# STC16.net
KiCad netlist of a schematic drawn in Altium Designer
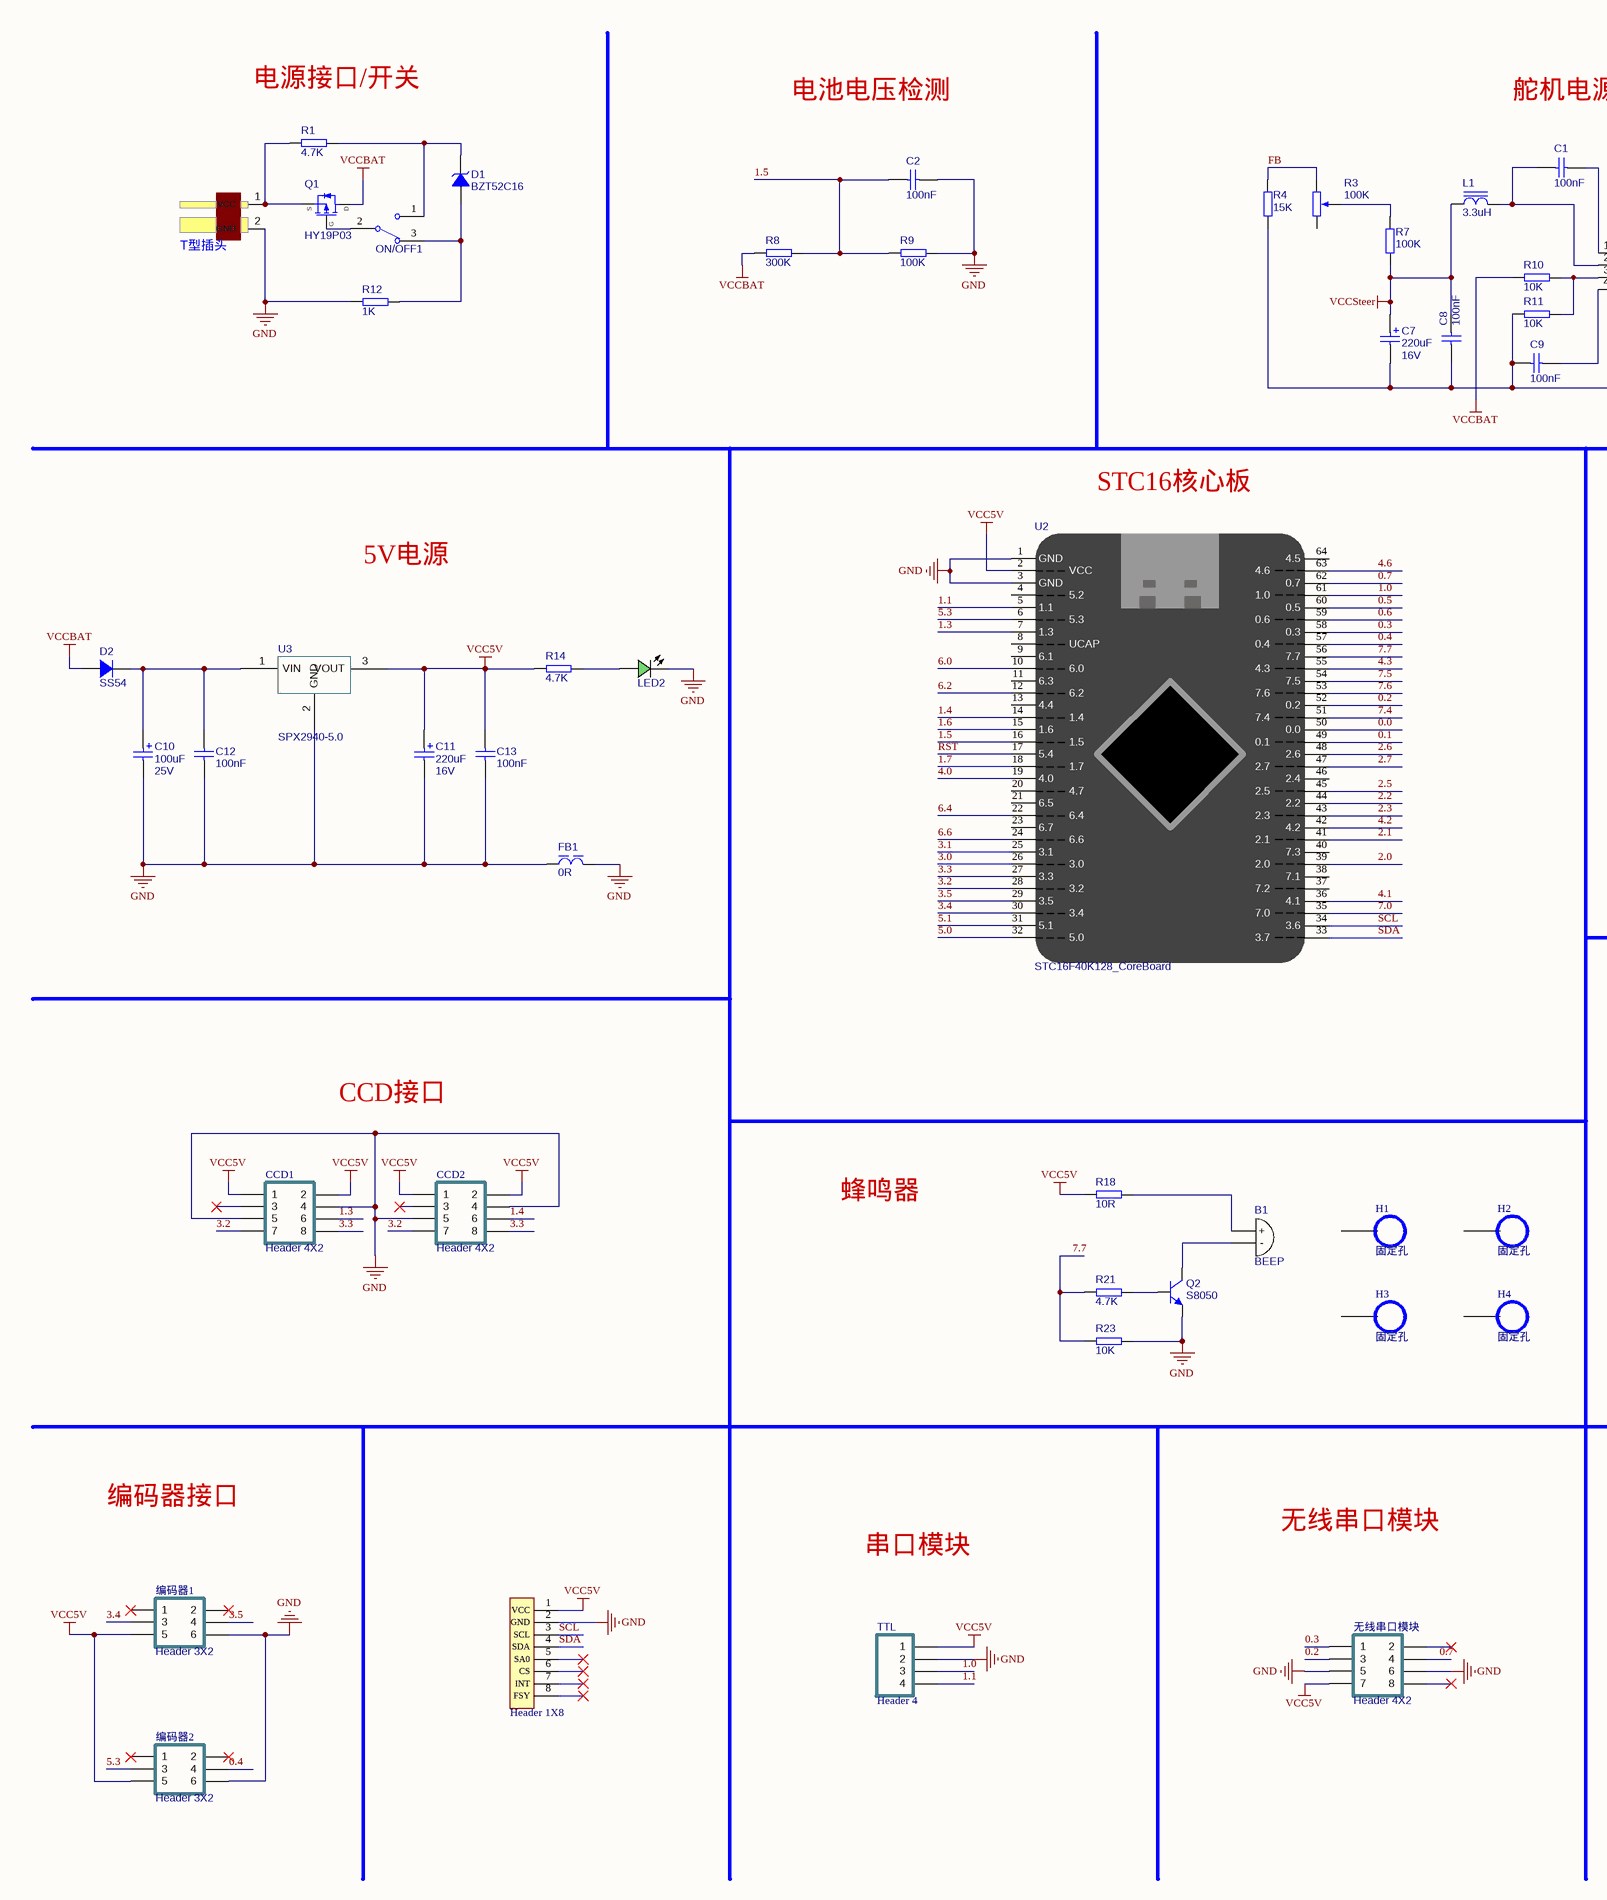
[diagram p0: STC16.SchDoc, left]
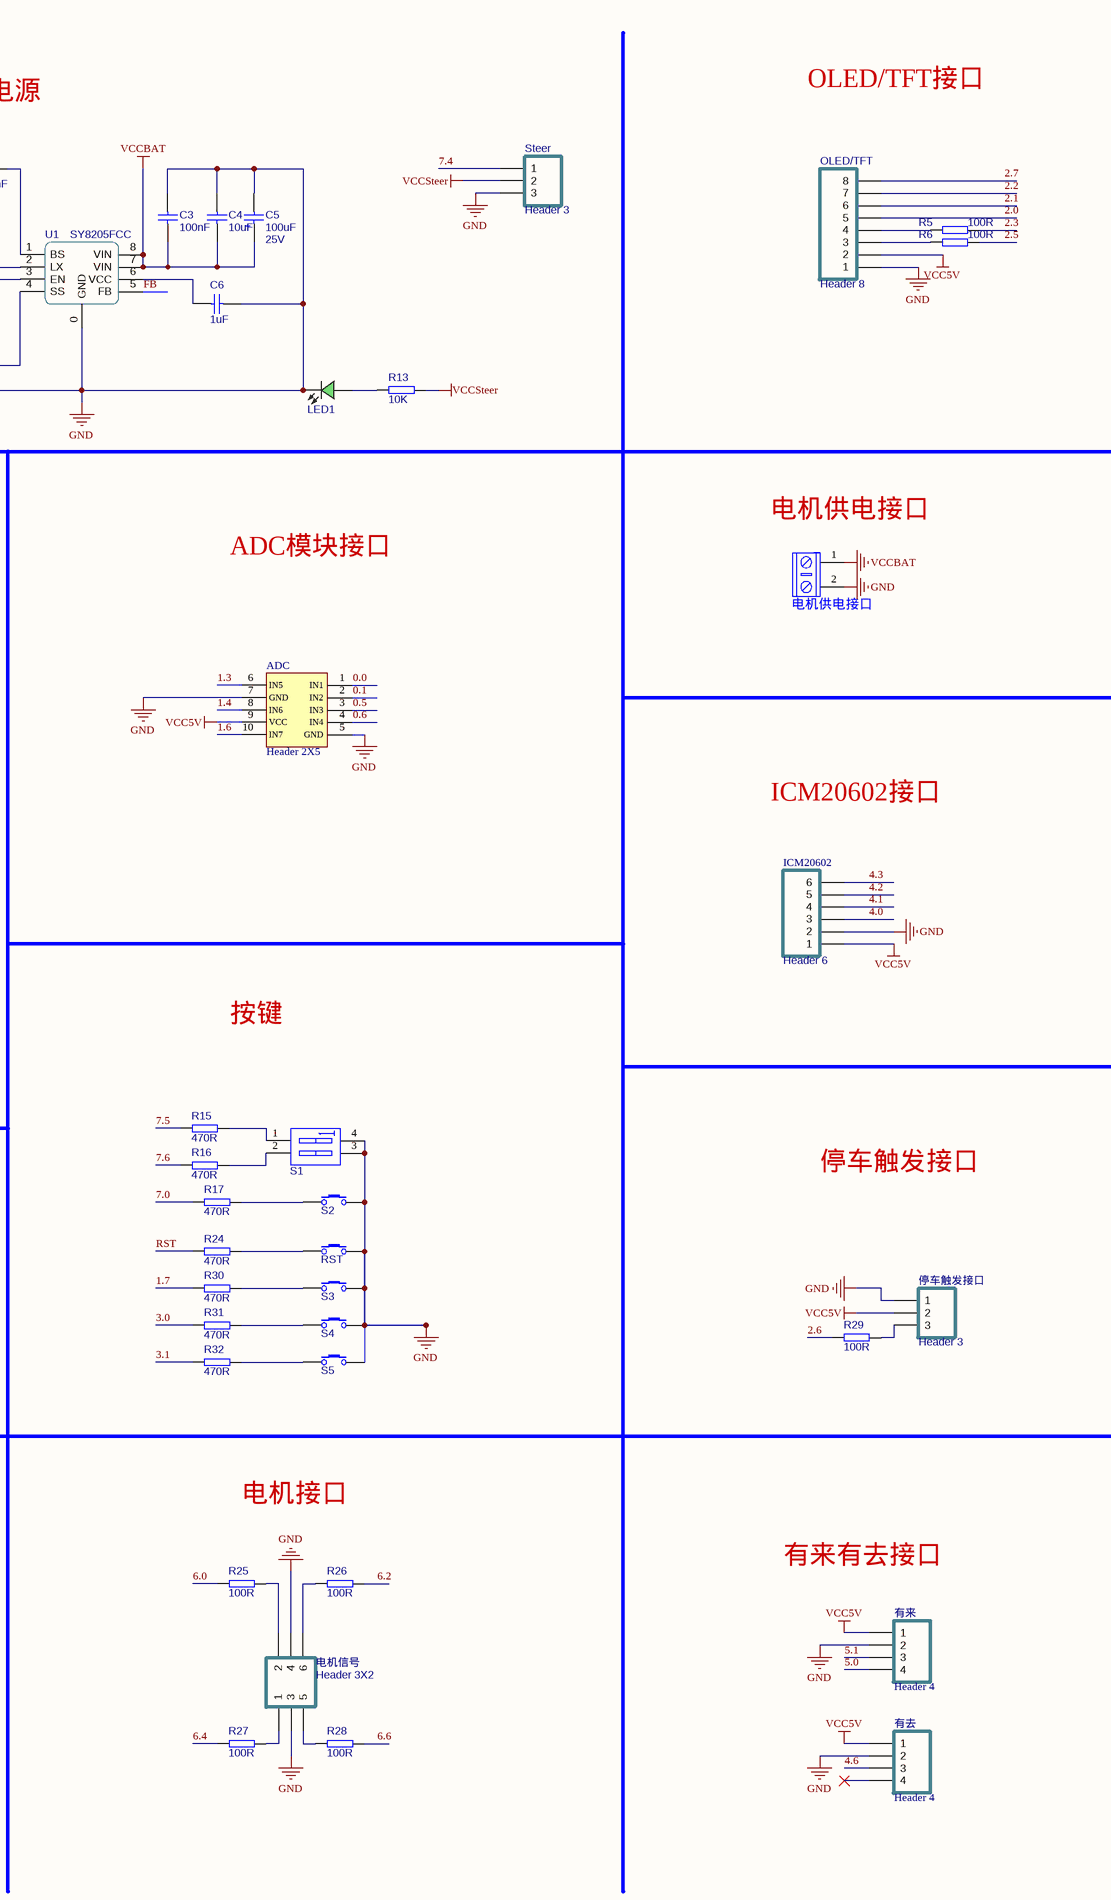
[diagram p1: STC16.SchDoc, right]

(export (version "E")
  (design (tool "Eeschema 10.0.6"))
  (components
    (comp (ref "ADC") (value "Header 2X5") (footprint "HDR2X5") (libsource (lib "STC16") (part "Header 2X5")))
    (comp (ref "B1")
      (value "BEEP")
      (footprint "BEEP 9x5.5mm")
      (description "蜂鸣器")
      (libsource (lib "STC16") (part "BEEP"))
    )
    (comp (ref "C1")
      (value "100nF")
      (footprint "0603_C")
      (description "贴片电容100nF")
      (fields
        (field (name "VOLTAGE") "50V")
        (field (name "TOLERANCE") "±10%")
        (field (name "PUBLISHER") "Altium Limited")
      )
      (libsource (lib "STC16") (part "Cap-Chip"))
    )
    (comp (ref "C2")
      (value "100nF")
      (footprint "0603_C")
      (description "贴片电容100nF")
      (fields
        (field (name "VOLTAGE") "50V")
        (field (name "TOLERANCE") "±10%")
        (field (name "PUBLISHER") "Altium Limited")
      )
      (libsource (lib "STC16") (part "Cap-Chip"))
    )
    (comp (ref "C3")
      (value "100nF")
      (footprint "0603_C")
      (description "贴片电容100nF")
      (fields
        (field (name "VOLTAGE") "50V")
        (field (name "TOLERANCE") "±10%")
        (field (name "PUBLISHER") "Altium Limited")
      )
      (libsource (lib "STC16") (part "Cap-Chip"))
    )
    (comp (ref "C4")
      (value "10uF")
      (footprint "0603_C")
      (description "贴片电容10uF")
      (fields
        (field (name "VOLTAGE") "50V")
        (field (name "TOLERANCE") "±10%")
        (field (name "PUBLISHER") "Altium Limited")
      )
      (libsource (lib "STC16") (part "Cap-Chip_2"))
    )
    (comp (ref "C5")
      (value "100uF")
      (footprint "CAPS6.3")
      (description "Polarized Capacitor (Radial) 100uF，25V")
      (fields
        (field (name "VOLTAGE") "25V")
        (field (name "Comment") "100uF 25V")
        (field (name "PUBLISHER") "Altium Limited")
      )
      (libsource (lib "STC16") (part "Cap-Solid"))
    )
    (comp (ref "C6")
      (value "1uF")
      (footprint "0603_C")
      (description "贴片电容1uF")
      (fields
        (field (name "VOLTAGE") "50V")
        (field (name "TOLERANCE") "±10%")
        (field (name "PUBLISHER") "Altium Limited")
      )
      (libsource (lib "STC16") (part "Cap-Chip_1"))
    )
    (comp (ref "C7")
      (value "220uF")
      (footprint "CAPS6.3")
      (description "Polarized Capacitor (Radial)  220uF 16V")
      (fields
        (field (name "VOLTAGE") "16V")
        (field (name "Comment") "220uF 16V")
        (field (name "PUBLISHER") "Altium Limited")
      )
      (libsource (lib "STC16") (part "Cap-Solid_1"))
    )
    (comp (ref "C8")
      (value "100nF")
      (footprint "0603_C")
      (description "贴片电容100nF")
      (fields
        (field (name "VOLTAGE") "50V")
        (field (name "TOLERANCE") "±10%")
        (field (name "PUBLISHER") "Altium Limited")
      )
      (libsource (lib "STC16") (part "Cap-Chip"))
    )
    (comp (ref "C9")
      (value "100nF")
      (footprint "0603_C")
      (description "贴片电容10uF")
      (fields
        (field (name "VOLTAGE") "50V")
        (field (name "TOLERANCE") "±10%")
        (field (name "PUBLISHER") "Altium Limited")
      )
      (libsource (lib "STC16") (part "Cap-Chip_2"))
    )
    (comp (ref "C10")
      (value "100uF")
      (footprint "CAPS6.3")
      (description "Polarized Capacitor (Radial) 100uF，25V")
      (fields
        (field (name "VOLTAGE") "25V")
        (field (name "Comment") "100uF 25V")
        (field (name "PUBLISHER") "Altium Limited")
      )
      (libsource (lib "STC16") (part "Cap-Solid"))
    )
    (comp (ref "C11")
      (value "220uF")
      (footprint "CAPS6.3")
      (description "Polarized Capacitor (Radial)  220uF 16V")
      (fields
        (field (name "VOLTAGE") "16V")
        (field (name "Comment") "220uF 16V")
        (field (name "PUBLISHER") "Altium Limited")
      )
      (libsource (lib "STC16") (part "Cap-Solid_1"))
    )
    (comp (ref "C12")
      (value "100nF")
      (footprint "0603_C")
      (description "贴片电容100nF")
      (fields
        (field (name "VOLTAGE") "50V")
        (field (name "TOLERANCE") "±10%")
        (field (name "PUBLISHER") "Altium Limited")
      )
      (libsource (lib "STC16") (part "Cap-Chip"))
    )
    (comp (ref "C13")
      (value "100nF")
      (footprint "0603_C")
      (description "贴片电容100nF")
      (fields
        (field (name "VOLTAGE") "50V")
        (field (name "TOLERANCE") "±10%")
        (field (name "PUBLISHER") "Altium Limited")
      )
      (libsource (lib "STC16") (part "Cap-Chip"))
    )
    (comp (ref "CCD1")
      (value "Header 4X2")
      (footprint "Female-Header-2.54-SMD-8")
      (description "Header, 4-Pin, Dual row")
      (fields (field (name "PUBLISHER") "Altium Limited"))
      (libsource (lib "STC16") (part "Header 4X2"))
    )
    (comp (ref "CCD2")
      (value "Header 4X2")
      (footprint "Female-Header-2.54-SMD-8")
      (description "Header, 4-Pin, Dual row")
      (fields (field (name "PUBLISHER") "Altium Limited"))
      (libsource (lib "STC16") (part "Header 4X2"))
    )
    (comp (ref "D1")
      (value "BZT52C16")
      (footprint "SOD-123-L")
      (description "TRANSIENT VOLTAGE  SUPPRESSOR DIODE")
      (fields (field (name "PUBLISHER") "Altium Limited"))
      (libsource (lib "STC16") (part "Diode TVS Uni-Dir"))
    )
    (comp (ref "D2")
      (value "SS54")
      (footprint "SMA[DO-214AC]")
      (description "普通二极管 Diode")
      (fields (field (name "PUBLISHER") "Altium Limited"))
      (libsource (lib "STC16") (part "Diode"))
    )
    (comp (ref "DCIN1")
      (value "T型插头")
      (footprint "Wired T-Header ThroughHole")
      (libsource (lib "STC16") (part "T_Header"))
    )
    (comp (ref "DCOUT1")
      (value "电机供电接口")
      (footprint "KF/WJ/DG 301-2p-5.0mm")
      (description "接线端子 2Pin")
      (libsource (lib "STC16") (part "KF/WJ/DG 30x"))
    )
    (comp (ref "FB1")
      (value "0R")
      (footprint "0603_R")
      (description "Chip Inductor, Ferrite-Core, Silkscreen Border")
      (fields (field (name "PUBLISHER") "Altium Limited"))
      (libsource (lib "STC16") (part "Ind Chip 2"))
    )
    (comp (ref "H1") (value "固定孔") (footprint "铜柱孔3") (libsource (lib "智能电子导盲系统") (part "固定孔")))
    (comp (ref "H2") (value "固定孔") (footprint "铜柱孔3") (libsource (lib "智能电子导盲系统") (part "固定孔")))
    (comp (ref "H3") (value "固定孔") (footprint "铜柱孔3") (libsource (lib "智能电子导盲系统") (part "固定孔")))
    (comp (ref "H4") (value "固定孔") (footprint "铜柱孔3") (libsource (lib "智能电子导盲系统") (part "固定孔")))
    (comp (ref "ICM20602")
      (value "Header 6")
      (footprint "HDR1X6")
      (description "Header, 6-Pin")
      (fields (field (name "PUBLISHER") "Altium Limited"))
      (libsource (lib "STC16") (part "Header 6"))
    )
    (comp (ref "L1")
      (value "3.3uH")
      (footprint "0630 TPC 7*7*3")
      (description "Power Inductor, Ferrite-Core")
      (fields (field (name "PUBLISHER") "Altium Limited"))
      (libsource (lib "STC16") (part "Ind Power"))
    )
    (comp (ref "LED1")
      (value "GREEN")
      (footprint "LEDC1608(0603)")
      (description "Typical Chip LED")
      (fields (field (name "PUBLISHER") "Altium Limited"))
      (libsource (lib "STC16") (part "LED Chip Green"))
    )
    (comp (ref "LED2")
      (value "GREEN")
      (footprint "LEDC1608(0603)")
      (description "Typical Chip LED")
      (fields (field (name "PUBLISHER") "Altium Limited"))
      (libsource (lib "STC16") (part "LED Chip Green"))
    )
    (comp (ref "MPU") (value "Header 1X8") (footprint "HDR1X8") (libsource (lib "STC16") (part "Header 1X8")))
    (comp (ref "OLED/TFT")
      (value "Header 8")
      (footprint "HDR1X8")
      (description "Header, 8-Pin")
      (fields (field (name "PUBLISHER") "Altium Limited"))
      (libsource (lib "STC16") (part "Header 8"))
    )
    (comp (ref "ON/OFF1")
      (value "SW-SPDT")
      (footprint "SS12D10")
      (description "单刀双掷开关 3脚船型、钮子、拨动开关 SPDT Subminiature Toggle Switch")
      (fields (field (name "PUBLISHER") "Altium Limited"))
      (libsource (lib "STC16") (part "SW-SPDT"))
    )
    (comp (ref "Q1")
      (value "HY19P03")
      (footprint "TO-252AA")
      (description "HY19P03 P-Channel MOSFET")
      (libsource (lib "STC16") (part "HY19P03"))
    )
    (comp (ref "Q2")
      (value "S8050")
      (footprint "SOT-23")
      (description "Discrete NPN Bipolar Transistor")
      (fields (field (name "PARTNUMBER") "S8050") (field (name "PUBLISHER") "Altium Limited"))
      (libsource (lib "STC16") (part "NPN S8050"))
    )
    (comp (ref "R1")
      (value "4.7K")
      (footprint "0603_R")
      (description "贴片电阻4.7K")
      (fields
        (field (name "TOLERANCE") "±1%")
        (field (name "Comment") "4.7K ±1%")
        (field (name "PUBLISHER") "Altium Limited")
      )
      (libsource (lib "STC16") (part "Res-Chip"))
    )
    (comp (ref "R3")
      (value "100K")
      (footprint "RESPOT3296")
      (description "可调电阻")
      (libsource (lib "STC16") (part "Res Adj 3p"))
    )
    (comp (ref "R4")
      (value "15K")
      (footprint "0603_R")
      (description "贴片电阻15K")
      (fields
        (field (name "TOLERANCE") "±1%")
        (field (name "Comment") "15K ±1%")
        (field (name "PUBLISHER") "Altium Limited")
      )
      (libsource (lib "SEEKFREE_Device") (part "Res-Chip_2"))
    )
    (comp (ref "R5")
      (value "100R")
      (footprint "0603_R")
      (description "贴片电阻100R")
      (fields
        (field (name "TOLERANCE") "±1%")
        (field (name "Comment") "100R ±1%")
        (field (name "PUBLISHER") "Altium Limited")
      )
      (libsource (lib "STC16") (part "Res-Chip_5"))
    )
    (comp (ref "R6")
      (value "100R")
      (footprint "0603_R")
      (description "贴片电阻100R")
      (fields
        (field (name "TOLERANCE") "±1%")
        (field (name "Comment") "100R ±1%")
        (field (name "PUBLISHER") "Altium Limited")
      )
      (libsource (lib "STC16") (part "Res-Chip_5"))
    )
    (comp (ref "R7")
      (value "100K")
      (footprint "0603_R")
      (description "贴片电阻10K")
      (fields
        (field (name "TOLERANCE") "±1%")
        (field (name "Comment") "100K ±1%")
        (field (name "PUBLISHER") "Altium Limited")
      )
      (libsource (lib "SEEKFREE_Device") (part "Res-Chip_3"))
    )
    (comp (ref "R8")
      (value "300K")
      (footprint "0603_R")
      (description "贴片电阻")
      (fields
        (field (name "TOLERANCE") "±1%")
        (field (name "Comment") "300K ±1%")
        (field (name "PUBLISHER") "Altium Limited")
      )
      (libsource (lib "STC16") (part "Res-Chip_7"))
    )
    (comp (ref "R9")
      (value "100K")
      (footprint "0603_R")
      (description "贴片电阻100K")
      (fields
        (field (name "TOLERANCE") "±1%")
        (field (name "Comment") "100K ±1%")
        (field (name "PUBLISHER") "Altium Limited")
      )
      (libsource (lib "STC16") (part "Res-Chip_1"))
    )
    (comp (ref "R10")
      (value "10K")
      (footprint "0603_R")
      (description "贴片电阻10K")
      (fields
        (field (name "TOLERANCE") "±1%")
        (field (name "Comment") "10K ±1%")
        (field (name "PUBLISHER") "Altium Limited")
      )
      (libsource (lib "SEEKFREE_Device") (part "Res-Chip_3"))
    )
    (comp (ref "R11")
      (value "10K")
      (footprint "0603_R")
      (description "贴片电阻10K")
      (fields
        (field (name "TOLERANCE") "±1%")
        (field (name "Comment") "10K ±1%")
        (field (name "PUBLISHER") "Altium Limited")
      )
      (libsource (lib "SEEKFREE_Device") (part "Res-Chip_3"))
    )
    (comp (ref "R12")
      (value "1K")
      (footprint "0603_R")
      (description "贴片电阻1K")
      (fields
        (field (name "TOLERANCE") "±1%")
        (field (name "Comment") "1K ±1%")
        (field (name "PUBLISHER") "Altium Limited")
      )
      (libsource (lib "STC16") (part "Res-Chip_4"))
    )
    (comp (ref "R13")
      (value "10K")
      (footprint "0603_R")
      (description "贴片电阻10K")
      (fields
        (field (name "TOLERANCE") "±1%")
        (field (name "Comment") "10K ±1%")
        (field (name "PUBLISHER") "Altium Limited")
      )
      (libsource (lib "SEEKFREE_Device") (part "Res-Chip_3"))
    )
    (comp (ref "R14")
      (value "4.7K")
      (footprint "0603_R")
      (description "贴片电阻4.7K")
      (fields
        (field (name "TOLERANCE") "±1%")
        (field (name "Comment") "4.7K ±1%")
        (field (name "PUBLISHER") "Altium Limited")
      )
      (libsource (lib "STC16") (part "Res-Chip"))
    )
    (comp (ref "R15")
      (value "470R")
      (footprint "0603_R")
      (description "贴片电阻")
      (fields
        (field (name "TOLERANCE") "±1%")
        (field (name "Comment") "470R ±1%")
        (field (name "PUBLISHER") "Altium Limited")
      )
      (libsource (lib "STC16") (part "Res-Chip_8"))
    )
    (comp (ref "R16")
      (value "470R")
      (footprint "0603_R")
      (description "贴片电阻")
      (fields
        (field (name "TOLERANCE") "±1%")
        (field (name "Comment") "470R ±1%")
        (field (name "PUBLISHER") "Altium Limited")
      )
      (libsource (lib "STC16") (part "Res-Chip_8"))
    )
    (comp (ref "R17")
      (value "470R")
      (footprint "0603_R")
      (description "贴片电阻")
      (fields
        (field (name "TOLERANCE") "±1%")
        (field (name "Comment") "470R ±1%")
        (field (name "PUBLISHER") "Altium Limited")
      )
      (libsource (lib "STC16") (part "Res-Chip_8"))
    )
    (comp (ref "R18")
      (value "10R")
      (footprint "0603_R")
      (description "贴片电阻")
      (fields
        (field (name "TOLERANCE") "±1%")
        (field (name "Comment") "10R ±1%")
        (field (name "PUBLISHER") "Altium Limited")
      )
      (libsource (lib "STC16") (part "Res-Chip_6"))
    )
    (comp (ref "R21")
      (value "4.7K")
      (footprint "0603_R")
      (description "贴片电阻4.7K")
      (fields
        (field (name "TOLERANCE") "±1%")
        (field (name "Comment") "4.7K ±1%")
        (field (name "PUBLISHER") "Altium Limited")
      )
      (libsource (lib "STC16") (part "Res-Chip"))
    )
    (comp (ref "R23")
      (value "10K")
      (footprint "0603_R")
      (description "贴片电阻10K")
      (fields
        (field (name "TOLERANCE") "±1%")
        (field (name "Comment") "10K ±1%")
        (field (name "PUBLISHER") "Altium Limited")
      )
      (libsource (lib "STC16") (part "Res-Chip_3"))
    )
    (comp (ref "R24")
      (value "470R")
      (footprint "0603_R")
      (description "贴片电阻")
      (fields
        (field (name "TOLERANCE") "±1%")
        (field (name "Comment") "470R ±1%")
        (field (name "PUBLISHER") "Altium Limited")
      )
      (libsource (lib "STC16") (part "Res-Chip_8"))
    )
    (comp (ref "R25")
      (value "100R")
      (footprint "0603_R")
      (description "贴片电阻100R")
      (fields
        (field (name "TOLERANCE") "±1%")
        (field (name "Comment") "100R ±1%")
        (field (name "PUBLISHER") "Altium Limited")
      )
      (libsource (lib "STC16") (part "Res-Chip_5"))
    )
    (comp (ref "R26")
      (value "100R")
      (footprint "0603_R")
      (description "贴片电阻100R")
      (fields
        (field (name "TOLERANCE") "±1%")
        (field (name "Comment") "100R ±1%")
        (field (name "PUBLISHER") "Altium Limited")
      )
      (libsource (lib "STC16") (part "Res-Chip_5"))
    )
    (comp (ref "R27")
      (value "100R")
      (footprint "0603_R")
      (description "贴片电阻100R")
      (fields
        (field (name "TOLERANCE") "±1%")
        (field (name "Comment") "100R ±1%")
        (field (name "PUBLISHER") "Altium Limited")
      )
      (libsource (lib "STC16") (part "Res-Chip_5"))
    )
    (comp (ref "R28")
      (value "100R")
      (footprint "0603_R")
      (description "贴片电阻100R")
      (fields
        (field (name "TOLERANCE") "±1%")
        (field (name "Comment") "100R ±1%")
        (field (name "PUBLISHER") "Altium Limited")
      )
      (libsource (lib "STC16") (part "Res-Chip_5"))
    )
    (comp (ref "R29")
      (value "100R")
      (footprint "0603_R")
      (description "贴片电阻100R")
      (fields
        (field (name "TOLERANCE") "±1%")
        (field (name "Comment") "100R ±1%")
        (field (name "PUBLISHER") "Altium Limited")
      )
      (libsource (lib "STC16") (part "Res-Chip_5"))
    )
    (comp (ref "R30")
      (value "470R")
      (footprint "0603_R")
      (description "贴片电阻")
      (fields
        (field (name "TOLERANCE") "±1%")
        (field (name "Comment") "470R ±1%")
        (field (name "PUBLISHER") "Altium Limited")
      )
      (libsource (lib "STC16") (part "Res-Chip_8"))
    )
    (comp (ref "R31")
      (value "470R")
      (footprint "0603_R")
      (description "贴片电阻")
      (fields
        (field (name "TOLERANCE") "±1%")
        (field (name "Comment") "470R ±1%")
        (field (name "PUBLISHER") "Altium Limited")
      )
      (libsource (lib "STC16") (part "Res-Chip_8"))
    )
    (comp (ref "R32")
      (value "470R")
      (footprint "0603_R")
      (description "贴片电阻")
      (fields
        (field (name "TOLERANCE") "±1%")
        (field (name "Comment") "470R ±1%")
        (field (name "PUBLISHER") "Altium Limited")
      )
      (libsource (lib "STC16") (part "Res-Chip_8"))
    )
    (comp (ref "RST")
      (value "Button")
      (footprint "PTS810-3*4-CurvePin")
      (description "按键")
      (fields (field (name "PUBLISHER") "Altium Limited"))
      (libsource (lib "STC16") (part "KEY"))
    )
    (comp (ref "S1")
      (value "SW DIP-2")
      (footprint "DIP4")
      (description "2位拨码开关")
      (fields (field (name "PUBLISHER") "Altium Limited"))
      (libsource (lib "STC16") (part "Code SW-2"))
    )
    (comp (ref "S2")
      (value "Button")
      (footprint "PTS810-3*4-CurvePin")
      (description "按键")
      (fields (field (name "PUBLISHER") "Altium Limited"))
      (libsource (lib "STC16") (part "KEY"))
    )
    (comp (ref "S3")
      (value "Button")
      (footprint "PTS810-3*4-CurvePin")
      (description "按键")
      (fields (field (name "PUBLISHER") "Altium Limited"))
      (libsource (lib "STC16") (part "KEY"))
    )
    (comp (ref "S4")
      (value "Button")
      (footprint "PTS810-3*4-CurvePin")
      (description "按键")
      (fields (field (name "PUBLISHER") "Altium Limited"))
      (libsource (lib "STC16") (part "KEY"))
    )
    (comp (ref "S5")
      (value "Button")
      (footprint "PTS810-3*4-CurvePin")
      (description "按键")
      (fields (field (name "PUBLISHER") "Altium Limited"))
      (libsource (lib "STC16") (part "KEY"))
    )
    (comp (ref "Steer")
      (value "Header 3")
      (footprint "HDR1X3")
      (description "Header, 3-Pin")
      (fields (field (name "PUBLISHER") "Altium Limited"))
      (libsource (lib "STC16") (part "Header 3"))
    )
    (comp (ref "TTL")
      (value "Header 4")
      (footprint "HDR1X4")
      (description "Header, 4-Pin")
      (fields (field (name "PUBLISHER") "Altium Limited"))
      (libsource (lib "") (part "Header 4_1"))
    )
    (comp (ref "U1")
      (value "SY8205FCC")
      (footprint "SOP-8E")
      (description "同步buck")
      (libsource (lib "STC16") (part "SY8205FCC"))
    )
    (comp (ref "U2")
      (value "STC16F40K128_CoreBoard")
      (footprint "STC16F40K128_CoreBoard")
      (description "逐飞科技 STC16F40K128核心板")
      (libsource (lib "STC16") (part "STC16F40K128_CoreBoard"))
    )
    (comp (ref "U3")
      (value "SPX2940-5.0")
      (footprint "TO-263-3")
      (description "5V LDO TO-263-3")
      (libsource (lib "STC16") (part "LM2940-5.0"))
    )
    (comp (ref "停车触发接口")
      (value "Header 3")
      (footprint "HDR1X3")
      (description "Header, 3-Pin")
      (fields (field (name "PUBLISHER") "Altium Limited"))
      (libsource (lib "STC16") (part "Header 3"))
    )
    (comp (ref "无线串口模块")
      (value "Header 4X2")
      (footprint "Female-Header-2.54-SMD-8")
      (description "Header, 4-Pin, Dual row")
      (fields (field (name "PUBLISHER") "Altium Limited"))
      (libsource (lib "STC16") (part "Header 4X2"))
    )
    (comp (ref "有去")
      (value "Header 4")
      (footprint "HDR1X4")
      (description "Header, 4-Pin")
      (fields (field (name "PUBLISHER") "Altium Limited"))
      (libsource (lib "STC16") (part "Header 4"))
    )
    (comp (ref "有来")
      (value "Header 4")
      (footprint "HDR1X4")
      (description "Header, 4-Pin")
      (fields (field (name "PUBLISHER") "Altium Limited"))
      (libsource (lib "STC16") (part "Header 4"))
    )
    (comp (ref "电机信号")
      (value "Header 3X2")
      (footprint "HDR2X3-M-SMT")
      (description "Header, 3-Pin, Dual row")
      (fields (field (name "PUBLISHER") "Altium Limited"))
      (libsource (lib "STC16") (part "Header 3X2"))
    )
    (comp (ref "编码器1")
      (value "Header 3X2")
      (footprint "HDR2X3-M-SMT")
      (description "Header, 3-Pin, Dual row")
      (fields (field (name "PUBLISHER") "Altium Limited"))
      (libsource (lib "") (part "Header 3X2_1"))
    )
    (comp (ref "编码器2")
      (value "Header 3X2")
      (footprint "HDR2X3-M-SMT")
      (description "Header, 3-Pin, Dual row")
      (fields (field (name "PUBLISHER") "Altium Limited"))
      (libsource (lib "") (part "Header 3X2_1"))
    )
  )
  (nets
    (net (code "1") (name "/0.0") (class "Default")
      (node (ref "ADC") (pin "1") (pinfunction "IN1_1") (pintype "passive"))
      (node (ref "U2") (pin "50") (pinfunction "0.0_50") (pintype "passive"))
    )
    (net (code "2") (name "/0.1") (class "Default")
      (node (ref "ADC") (pin "2") (pinfunction "IN2_2") (pintype "passive"))
      (node (ref "U2") (pin "49") (pinfunction "0.1_49") (pintype "passive"))
    )
    (net (code "3") (name "/0.2") (class "Default")
      (node (ref "U2") (pin "52") (pinfunction "0.2_52") (pintype "passive"))
      (node (ref "无线串口模块") (pin "3") (pinfunction "3_3") (pintype "passive"))
    )
    (net (code "4") (name "/0.3") (class "Default")
      (node (ref "U2") (pin "58") (pinfunction "0.3_58") (pintype "passive"))
      (node (ref "无线串口模块") (pin "1") (pinfunction "1_1") (pintype "passive"))
    )
    (net (code "5") (name "/0.4") (class "Default")
      (node (ref "U2") (pin "57") (pinfunction "0.4_57") (pintype "passive"))
      (node (ref "编码器2") (pin "4") (pinfunction "4_4") (pintype "passive"))
    )
    (net (code "6") (name "/0.5") (class "Default")
      (node (ref "ADC") (pin "3") (pinfunction "IN3_3") (pintype "passive"))
      (node (ref "U2") (pin "60") (pinfunction "0.5_60") (pintype "passive"))
    )
    (net (code "7") (name "/0.6") (class "Default")
      (node (ref "ADC") (pin "4") (pinfunction "IN4_4") (pintype "passive"))
      (node (ref "U2") (pin "59") (pinfunction "0.6_59") (pintype "passive"))
    )
    (net (code "8") (name "/0.7") (class "Default")
      (node (ref "U2") (pin "62") (pinfunction "0.7_62") (pintype "passive"))
      (node (ref "无线串口模块") (pin "4") (pinfunction "4_4") (pintype "passive"))
    )
    (net (code "9") (name "/1.0") (class "Default")
      (node (ref "TTL") (pin "3") (pinfunction "3_3") (pintype "passive"))
      (node (ref "U2") (pin "61") (pinfunction "1.0_61") (pintype "passive"))
    )
    (net (code "10") (name "/1.1") (class "Default")
      (node (ref "TTL") (pin "4") (pinfunction "4_4") (pintype "passive"))
      (node (ref "U2") (pin "5") (pinfunction "1.1_5") (pintype "passive"))
    )
    (net (code "11") (name "/1.3") (class "Default")
      (node (ref "ADC") (pin "6") (pinfunction "IN5_6") (pintype "passive"))
      (node (ref "CCD1") (pin "6") (pinfunction "6_6") (pintype "passive"))
      (node (ref "U2") (pin "7") (pinfunction "1.3_7") (pintype "passive"))
    )
    (net (code "12") (name "/1.4") (class "Default")
      (node (ref "ADC") (pin "8") (pinfunction "IN6_8") (pintype "passive"))
      (node (ref "CCD2") (pin "6") (pinfunction "6_6") (pintype "passive"))
      (node (ref "U2") (pin "14") (pinfunction "1.4_14") (pintype "passive"))
    )
    (net (code "13") (name "/1.5") (class "Default")
      (node (ref "C2") (pin "1") (pinfunction "1_1") (pintype "passive"))
      (node (ref "R8") (pin "2") (pinfunction "2_2") (pintype "passive"))
      (node (ref "R9") (pin "1") (pinfunction "1_1") (pintype "passive"))
      (node (ref "U2") (pin "16") (pinfunction "1.5_16") (pintype "passive"))
    )
    (net (code "14") (name "/1.6") (class "Default")
      (node (ref "ADC") (pin "10") (pinfunction "IN7_10") (pintype "passive"))
      (node (ref "U2") (pin "15") (pinfunction "1.6_15") (pintype "passive"))
    )
    (net (code "15") (name "/1.7") (class "Default")
      (node (ref "R30") (pin "1") (pinfunction "1_1") (pintype "passive"))
      (node (ref "U2") (pin "18") (pinfunction "1.7_18") (pintype "passive"))
    )
    (net (code "16") (name "/2.0") (class "Default")
      (node (ref "OLED/TFT") (pin "5") (pinfunction "5_5") (pintype "passive"))
      (node (ref "U2") (pin "39") (pinfunction "2.0_39") (pintype "passive"))
    )
    (net (code "17") (name "/2.1") (class "Default")
      (node (ref "OLED/TFT") (pin "6") (pinfunction "6_6") (pintype "passive"))
      (node (ref "U2") (pin "41") (pinfunction "2.1_41") (pintype "passive"))
    )
    (net (code "18") (name "/2.2") (class "Default")
      (node (ref "OLED/TFT") (pin "7") (pinfunction "7_7") (pintype "passive"))
      (node (ref "U2") (pin "44") (pinfunction "2.2_44") (pintype "passive"))
    )
    (net (code "19") (name "/2.3") (class "Default")
      (node (ref "R5") (pin "2") (pinfunction "2_2") (pintype "passive"))
      (node (ref "U2") (pin "43") (pinfunction "2.3_43") (pintype "passive"))
    )
    (net (code "20") (name "/2.5") (class "Default")
      (node (ref "R6") (pin "2") (pinfunction "2_2") (pintype "passive"))
      (node (ref "U2") (pin "45") (pinfunction "2.5_45") (pintype "passive"))
    )
    (net (code "21") (name "/2.6") (class "Default")
      (node (ref "R29") (pin "1") (pinfunction "1_1") (pintype "passive"))
      (node (ref "U2") (pin "48") (pinfunction "2.6_48") (pintype "passive"))
    )
    (net (code "22") (name "/2.7") (class "Default")
      (node (ref "OLED/TFT") (pin "8") (pinfunction "8_8") (pintype "passive"))
      (node (ref "U2") (pin "47") (pinfunction "2.7_47") (pintype "passive"))
    )
    (net (code "23") (name "/3.0") (class "Default")
      (node (ref "R31") (pin "1") (pinfunction "1_1") (pintype "passive"))
      (node (ref "U2") (pin "26") (pinfunction "3.0_26") (pintype "passive"))
    )
    (net (code "24") (name "/3.1") (class "Default")
      (node (ref "R32") (pin "1") (pinfunction "1_1") (pintype "passive"))
      (node (ref "U2") (pin "25") (pinfunction "3.1_25") (pintype "passive"))
    )
    (net (code "25") (name "/3.2") (class "Default")
      (node (ref "CCD1") (pin "7") (pinfunction "7_7") (pintype "passive"))
      (node (ref "CCD2") (pin "7") (pinfunction "7_7") (pintype "passive"))
      (node (ref "U2") (pin "28") (pinfunction "3.2_28") (pintype "passive"))
    )
    (net (code "26") (name "/3.3") (class "Default")
      (node (ref "CCD1") (pin "8") (pinfunction "8_8") (pintype "passive"))
      (node (ref "CCD2") (pin "8") (pinfunction "8_8") (pintype "passive"))
      (node (ref "U2") (pin "27") (pinfunction "3.3_27") (pintype "passive"))
    )
    (net (code "27") (name "/3.4") (class "Default")
      (node (ref "U2") (pin "30") (pinfunction "3.4_30") (pintype "passive"))
      (node (ref "编码器1") (pin "3") (pinfunction "3_3") (pintype "passive"))
    )
    (net (code "28") (name "/3.5") (class "Default")
      (node (ref "U2") (pin "29") (pinfunction "3.5_29") (pintype "passive"))
      (node (ref "编码器1") (pin "4") (pinfunction "4_4") (pintype "passive"))
    )
    (net (code "29") (name "/4.0") (class "Default")
      (node (ref "ICM20602") (pin "3") (pinfunction "3_3") (pintype "passive"))
      (node (ref "U2") (pin "19") (pinfunction "4.0_19") (pintype "passive"))
    )
    (net (code "30") (name "/4.1") (class "Default")
      (node (ref "ICM20602") (pin "4") (pinfunction "4_4") (pintype "passive"))
      (node (ref "U2") (pin "36") (pinfunction "4.1_36") (pintype "passive"))
    )
    (net (code "31") (name "/4.2") (class "Default")
      (node (ref "ICM20602") (pin "5") (pinfunction "5_5") (pintype "passive"))
      (node (ref "U2") (pin "42") (pinfunction "4.2_42") (pintype "passive"))
    )
    (net (code "32") (name "/4.3") (class "Default")
      (node (ref "ICM20602") (pin "6") (pinfunction "6_6") (pintype "passive"))
      (node (ref "U2") (pin "55") (pinfunction "4.3_55") (pintype "passive"))
    )
    (net (code "33") (name "/4.6") (class "Default")
      (node (ref "U2") (pin "63") (pinfunction "4.6_63") (pintype "passive"))
      (node (ref "有去") (pin "3") (pinfunction "3_3") (pintype "passive"))
    )
    (net (code "34") (name "/5.0") (class "Default")
      (node (ref "U2") (pin "32") (pinfunction "5.0_32") (pintype "passive"))
      (node (ref "有来") (pin "4") (pinfunction "4_4") (pintype "passive"))
    )
    (net (code "35") (name "/5.1") (class "Default")
      (node (ref "U2") (pin "31") (pinfunction "5.1_31") (pintype "passive"))
      (node (ref "有来") (pin "3") (pinfunction "3_3") (pintype "passive"))
    )
    (net (code "36") (name "/5.3") (class "Default")
      (node (ref "U2") (pin "6") (pinfunction "5.3_6") (pintype "passive"))
      (node (ref "编码器2") (pin "3") (pinfunction "3_3") (pintype "passive"))
    )
    (net (code "37") (name "/6.0") (class "Default")
      (node (ref "R25") (pin "2") (pinfunction "2_2") (pintype "passive"))
      (node (ref "U2") (pin "10") (pinfunction "6.0_10") (pintype "passive"))
    )
    (net (code "38") (name "/6.2") (class "Default")
      (node (ref "R26") (pin "1") (pinfunction "1_1") (pintype "passive"))
      (node (ref "U2") (pin "12") (pinfunction "6.2_12") (pintype "passive"))
    )
    (net (code "39") (name "/6.4") (class "Default")
      (node (ref "R27") (pin "2") (pinfunction "2_2") (pintype "passive"))
      (node (ref "U2") (pin "22") (pinfunction "6.4_22") (pintype "passive"))
    )
    (net (code "40") (name "/6.6") (class "Default")
      (node (ref "R28") (pin "1") (pinfunction "1_1") (pintype "passive"))
      (node (ref "U2") (pin "24") (pinfunction "6.6_24") (pintype "passive"))
    )
    (net (code "41") (name "/7.0") (class "Default")
      (node (ref "R17") (pin "1") (pinfunction "1_1") (pintype "passive"))
      (node (ref "U2") (pin "35") (pinfunction "7.0_35") (pintype "passive"))
    )
    (net (code "42") (name "/7.4") (class "Default")
      (node (ref "Steer") (pin "1") (pinfunction "1_1") (pintype "passive"))
      (node (ref "U2") (pin "51") (pinfunction "7.4_51") (pintype "passive"))
    )
    (net (code "43") (name "/7.5") (class "Default")
      (node (ref "R15") (pin "1") (pinfunction "1_1") (pintype "passive"))
      (node (ref "U2") (pin "54") (pinfunction "7.5_54") (pintype "passive"))
    )
    (net (code "44") (name "/7.6") (class "Default")
      (node (ref "R16") (pin "1") (pinfunction "1_1") (pintype "passive"))
      (node (ref "U2") (pin "53") (pinfunction "7.6_53") (pintype "passive"))
    )
    (net (code "45") (name "/7.7") (class "Default")
      (node (ref "R21") (pin "1") (pinfunction "1_1") (pintype "passive"))
      (node (ref "R23") (pin "1") (pinfunction "1_1") (pintype "passive"))
      (node (ref "U2") (pin "56") (pinfunction "7.7_56") (pintype "passive"))
    )
    (net (code "46") (name "/FB") (class "Default")
      (node (ref "R3") (pin "2") (pinfunction "BOT_2") (pintype "passive"))
      (node (ref "R4") (pin "2") (pinfunction "2_2") (pintype "passive"))
      (node (ref "U1") (pin "5") (pinfunction "FB_5") (pintype "passive"))
    )
    (net (code "47") (name "/RST") (class "Default")
      (node (ref "R24") (pin "1") (pinfunction "1_1") (pintype "passive"))
      (node (ref "U2") (pin "17") (pinfunction "5.4_17") (pintype "passive"))
    )
    (net (code "48") (name "/SCL") (class "Default")
      (node (ref "MPU") (pin "3") (pinfunction "SCL_3") (pintype "passive"))
      (node (ref "U2") (pin "34") (pinfunction "3.6_34") (pintype "passive"))
    )
    (net (code "49") (name "/SDA") (class "Default")
      (node (ref "MPU") (pin "4") (pinfunction "SDA_4") (pintype "passive"))
      (node (ref "U2") (pin "33") (pinfunction "3.7_33") (pintype "passive"))
    )
    (net (code "50") (name "GND") (class "Default")
      (node (ref "ADC") (pin "5") (pinfunction "GND_5") (pintype "passive"))
      (node (ref "ADC") (pin "7") (pinfunction "GND_7") (pintype "passive"))
      (node (ref "C10") (pin "2") (pinfunction "2_2") (pintype "passive"))
      (node (ref "C11") (pin "2") (pinfunction "2_2") (pintype "passive"))
      (node (ref "C12") (pin "1") (pinfunction "1_1") (pintype "passive"))
      (node (ref "C13") (pin "1") (pinfunction "1_1") (pintype "passive"))
      (node (ref "C2") (pin "2") (pinfunction "2_2") (pintype "passive"))
      (node (ref "C3") (pin "1") (pinfunction "1_1") (pintype "passive"))
      (node (ref "C4") (pin "2") (pinfunction "2_2") (pintype "passive"))
      (node (ref "C5") (pin "2") (pinfunction "2_2") (pintype "passive"))
      (node (ref "C6") (pin "2") (pinfunction "2_2") (pintype "passive"))
      (node (ref "C7") (pin "2") (pinfunction "2_2") (pintype "passive"))
      (node (ref "C8") (pin "1") (pinfunction "1_1") (pintype "passive"))
      (node (ref "C9") (pin "1") (pinfunction "1_1") (pintype "passive"))
      (node (ref "CCD1") (pin "4") (pinfunction "4_4") (pintype "passive"))
      (node (ref "CCD1") (pin "5") (pinfunction "5_5") (pintype "passive"))
      (node (ref "CCD2") (pin "4") (pinfunction "4_4") (pintype "passive"))
      (node (ref "CCD2") (pin "5") (pinfunction "5_5") (pintype "passive"))
      (node (ref "DCIN1") (pin "2") (pinfunction "GND_2") (pintype "passive"))
      (node (ref "DCOUT1") (pin "2") (pinfunction "2_2") (pintype "passive"))
      (node (ref "FB1") (pin "1") (pinfunction "1_1") (pintype "passive"))
      (node (ref "FB1") (pin "2") (pinfunction "2_2") (pintype "passive"))
      (node (ref "ICM20602") (pin "2") (pinfunction "2_2") (pintype "passive"))
      (node (ref "LED1") (pin "C") (pinfunction "C_C") (pintype "passive"))
      (node (ref "LED2") (pin "C") (pinfunction "C_C") (pintype "passive"))
      (node (ref "MPU") (pin "2") (pinfunction "GND_2") (pintype "passive"))
      (node (ref "OLED/TFT") (pin "1") (pinfunction "1_1") (pintype "passive"))
      (node (ref "Q2") (pin "2") (pinfunction "E_2") (pintype "passive"))
      (node (ref "R11") (pin "2") (pinfunction "2_2") (pintype "passive"))
      (node (ref "R12") (pin "1") (pinfunction "1_1") (pintype "passive"))
      (node (ref "R23") (pin "2") (pinfunction "2_2") (pintype "passive"))
      (node (ref "R4") (pin "1") (pinfunction "1_1") (pintype "passive"))
      (node (ref "R9") (pin "2") (pinfunction "2_2") (pintype "passive"))
      (node (ref "RST") (pin "1") (pinfunction "1_1") (pintype "passive"))
      (node (ref "S1") (pin "3") (pinfunction "B2_3") (pintype "passive"))
      (node (ref "S1") (pin "4") (pinfunction "B1_4") (pintype "passive"))
      (node (ref "S2") (pin "1") (pinfunction "1_1") (pintype "passive"))
      (node (ref "S3") (pin "1") (pinfunction "1_1") (pintype "passive"))
      (node (ref "S4") (pin "1") (pinfunction "1_1") (pintype "passive"))
      (node (ref "S5") (pin "1") (pinfunction "1_1") (pintype "passive"))
      (node (ref "Steer") (pin "3") (pinfunction "3_3") (pintype "passive"))
      (node (ref "TTL") (pin "2") (pinfunction "2_2") (pintype "passive"))
      (node (ref "U1") (pin "0") (pinfunction "GND_0") (pintype "passive"))
      (node (ref "U2") (pin "1") (pinfunction "GND_1") (pintype "passive"))
      (node (ref "U2") (pin "3") (pinfunction "GND_3") (pintype "passive"))
      (node (ref "U3") (pin "2") (pinfunction "GND_2") (pintype "passive"))
      (node (ref "停车触发接口") (pin "1") (pinfunction "1_1") (pintype "passive"))
      (node (ref "无线串口模块") (pin "5") (pinfunction "5_5") (pintype "passive"))
      (node (ref "无线串口模块") (pin "6") (pinfunction "6_6") (pintype "passive"))
      (node (ref "有去") (pin "2") (pinfunction "2_2") (pintype "passive"))
      (node (ref "有来") (pin "2") (pinfunction "2_2") (pintype "passive"))
      (node (ref "电机信号") (pin "3") (pinfunction "3_3") (pintype "passive"))
      (node (ref "电机信号") (pin "4") (pinfunction "4_4") (pintype "passive"))
      (node (ref "编码器1") (pin "6") (pinfunction "6_6") (pintype "passive"))
      (node (ref "编码器2") (pin "6") (pinfunction "6_6") (pintype "passive"))
    )
    (net (code "51") (name "Net-(B1-+)") (class "Default")
      (node (ref "B1") (pin "1") (pinfunction "+_1") (pintype "passive"))
      (node (ref "R18") (pin "2") (pinfunction "2_2") (pintype "passive"))
    )
    (net (code "52") (name "Net-(B1--)") (class "Default")
      (node (ref "B1") (pin "2") (pinfunction "-_2") (pintype "passive"))
      (node (ref "Q2") (pin "3") (pinfunction "C_3") (pintype "passive"))
    )
    (net (code "53") (name "Net-(D1-PadA)") (class "Default")
      (node (ref "D1") (pin "A") (pinfunction "A_A") (pintype "passive"))
      (node (ref "ON/OFF1") (pin "3") (pintype "passive"))
      (node (ref "R12") (pin "2") (pinfunction "2_2") (pintype "passive"))
    )
    (net (code "54") (name "Net-(D1-PadK)") (class "Default")
      (node (ref "D1") (pin "K") (pinfunction "K_K") (pintype "passive"))
      (node (ref "ON/OFF1") (pin "1") (pintype "passive"))
      (node (ref "R1") (pin "2") (pinfunction "2_2") (pintype "passive"))
    )
    (net (code "55") (name "Net-(DCIN1-VCC)") (class "Default")
      (node (ref "DCIN1") (pin "1") (pinfunction "VCC_1") (pintype "passive"))
      (node (ref "Q1") (pin "3") (pinfunction "S_3") (pintype "passive"))
      (node (ref "R1") (pin "1") (pinfunction "1_1") (pintype "passive"))
    )
    (net (code "56") (name "Net-(LED1-PadA)") (class "Default")
      (node (ref "LED1") (pin "A") (pinfunction "A_A") (pintype "passive"))
      (node (ref "R13") (pin "2") (pinfunction "2_2") (pintype "passive"))
    )
    (net (code "57") (name "Net-(LED2-PadA)") (class "Default")
      (node (ref "LED2") (pin "A") (pinfunction "A_A") (pintype "passive"))
      (node (ref "R14") (pin "2") (pinfunction "2_2") (pintype "passive"))
    )
    (net (code "58") (name "Net-(OLED/TFT-Pad3)") (class "Default")
      (node (ref "OLED/TFT") (pin "3") (pinfunction "3_3") (pintype "passive"))
      (node (ref "R6") (pin "1") (pinfunction "1_1") (pintype "passive"))
    )
    (net (code "59") (name "Net-(OLED/TFT-Pad4)") (class "Default")
      (node (ref "OLED/TFT") (pin "4") (pinfunction "4_4") (pintype "passive"))
      (node (ref "R5") (pin "1") (pinfunction "1_1") (pintype "passive"))
    )
    (net (code "60") (name "Net-(Q1-G)") (class "Default")
      (node (ref "ON/OFF1") (pin "2") (pintype "passive"))
      (node (ref "Q1") (pin "2") (pinfunction "G_2") (pintype "passive"))
    )
    (net (code "61") (name "Net-(Q2-B)") (class "Default")
      (node (ref "Q2") (pin "1") (pinfunction "B_1") (pintype "passive"))
      (node (ref "R21") (pin "2") (pinfunction "2_2") (pintype "passive"))
    )
    (net (code "62") (name "Net-(R3-PadADJ)") (class "Default")
      (node (ref "R3") (pin "ADJ") (pinfunction "ADJ_ADJ") (pintype "passive"))
      (node (ref "R7") (pin "2") (pinfunction "2_2") (pintype "passive"))
    )
    (net (code "63") (name "Net-(R17-Pad2)") (class "Default")
      (node (ref "R17") (pin "2") (pinfunction "2_2") (pintype "passive"))
      (node (ref "S2") (pin "2") (pinfunction "2_2") (pintype "passive"))
    )
    (net (code "64") (name "Net-(R24-Pad2)") (class "Default")
      (node (ref "R24") (pin "2") (pinfunction "2_2") (pintype "passive"))
      (node (ref "RST") (pin "2") (pinfunction "2_2") (pintype "passive"))
    )
    (net (code "65") (name "Net-(R25-Pad1)") (class "Default")
      (node (ref "R25") (pin "1") (pinfunction "1_1") (pintype "passive"))
      (node (ref "电机信号") (pin "2") (pinfunction "2_2") (pintype "passive"))
    )
    (net (code "66") (name "Net-(R26-Pad2)") (class "Default")
      (node (ref "R26") (pin "2") (pinfunction "2_2") (pintype "passive"))
      (node (ref "电机信号") (pin "6") (pinfunction "6_6") (pintype "passive"))
    )
    (net (code "67") (name "Net-(R27-Pad1)") (class "Default")
      (node (ref "R27") (pin "1") (pinfunction "1_1") (pintype "passive"))
      (node (ref "电机信号") (pin "1") (pinfunction "1_1") (pintype "passive"))
    )
    (net (code "68") (name "Net-(R28-Pad2)") (class "Default")
      (node (ref "R28") (pin "2") (pinfunction "2_2") (pintype "passive"))
      (node (ref "电机信号") (pin "5") (pinfunction "5_5") (pintype "passive"))
    )
    (net (code "69") (name "Net-(R29-Pad2)") (class "Default")
      (node (ref "R29") (pin "2") (pinfunction "2_2") (pintype "passive"))
      (node (ref "停车触发接口") (pin "3") (pinfunction "3_3") (pintype "passive"))
    )
    (net (code "70") (name "Net-(R30-Pad2)") (class "Default")
      (node (ref "R30") (pin "2") (pinfunction "2_2") (pintype "passive"))
      (node (ref "S3") (pin "2") (pinfunction "2_2") (pintype "passive"))
    )
    (net (code "71") (name "Net-(R31-Pad2)") (class "Default")
      (node (ref "R31") (pin "2") (pinfunction "2_2") (pintype "passive"))
      (node (ref "S4") (pin "2") (pinfunction "2_2") (pintype "passive"))
    )
    (net (code "72") (name "Net-(R32-Pad2)") (class "Default")
      (node (ref "R32") (pin "2") (pinfunction "2_2") (pintype "passive"))
      (node (ref "S5") (pin "2") (pinfunction "2_2") (pintype "passive"))
    )
    (net (code "73") (name "Net-(S1-A1)") (class "Default")
      (node (ref "R15") (pin "2") (pinfunction "2_2") (pintype "passive"))
      (node (ref "S1") (pin "1") (pinfunction "A1_1") (pintype "passive"))
    )
    (net (code "74") (name "Net-(S1-A2)") (class "Default")
      (node (ref "R16") (pin "2") (pinfunction "2_2") (pintype "passive"))
      (node (ref "S1") (pin "2") (pinfunction "A2_2") (pintype "passive"))
    )
    (net (code "75") (name "Net-(U1-BS)") (class "Default")
      (node (ref "C1") (pin "1") (pinfunction "1_1") (pintype "passive"))
      (node (ref "U1") (pin "1") (pinfunction "BS_1") (pintype "passive"))
    )
    (net (code "76") (name "Net-(U1-EN)") (class "Default")
      (node (ref "R10") (pin "1") (pinfunction "1_1") (pintype "passive"))
      (node (ref "R11") (pin "1") (pinfunction "1_1") (pintype "passive"))
      (node (ref "U1") (pin "3") (pinfunction "EN_3") (pintype "passive"))
    )
    (net (code "77") (name "Net-(U1-LX)") (class "Default")
      (node (ref "C1") (pin "2") (pinfunction "2_2") (pintype "passive"))
      (node (ref "L1") (pin "2") (pinfunction "2_2") (pintype "passive"))
      (node (ref "U1") (pin "2") (pinfunction "LX_2") (pintype "passive"))
    )
    (net (code "78") (name "Net-(U1-SS)") (class "Default")
      (node (ref "C9") (pin "2") (pinfunction "2_2") (pintype "passive"))
      (node (ref "U1") (pin "4") (pinfunction "SS_4") (pintype "passive"))
    )
    (net (code "79") (name "Net-(U1-VCC)") (class "Default")
      (node (ref "C6") (pin "1") (pinfunction "1_1") (pintype "passive"))
      (node (ref "U1") (pin "6") (pinfunction "VCC_6") (pintype "passive"))
    )
    (net (code "80") (name "Net-(U3-VIN)") (class "Default")
      (node (ref "C10") (pin "1") (pinfunction "1_1") (pintype "passive"))
      (node (ref "C12") (pin "2") (pinfunction "2_2") (pintype "passive"))
      (node (ref "D2") (pin "K") (pinfunction "K_K") (pintype "passive"))
      (node (ref "U3") (pin "1") (pinfunction "VIN_1") (pintype "passive"))
    )
    (net (code "81") (name "VCC5V") (class "Default")
      (node (ref "ADC") (pin "9") (pinfunction "VCC_9") (pintype "passive"))
      (node (ref "C11") (pin "1") (pinfunction "1_1") (pintype "passive"))
      (node (ref "C13") (pin "2") (pinfunction "2_2") (pintype "passive"))
      (node (ref "CCD1") (pin "1") (pinfunction "1_1") (pintype "passive"))
      (node (ref "CCD1") (pin "2") (pinfunction "2_2") (pintype "passive"))
      (node (ref "CCD2") (pin "1") (pinfunction "1_1") (pintype "passive"))
      (node (ref "CCD2") (pin "2") (pinfunction "2_2") (pintype "passive"))
      (node (ref "ICM20602") (pin "1") (pinfunction "1_1") (pintype "passive"))
      (node (ref "MPU") (pin "1") (pinfunction "VCC_1") (pintype "passive"))
      (node (ref "OLED/TFT") (pin "2") (pinfunction "2_2") (pintype "passive"))
      (node (ref "R14") (pin "1") (pinfunction "1_1") (pintype "passive"))
      (node (ref "R18") (pin "1") (pinfunction "1_1") (pintype "passive"))
      (node (ref "TTL") (pin "1") (pinfunction "1_1") (pintype "passive"))
      (node (ref "U2") (pin "2") (pinfunction "VCC_2") (pintype "passive"))
      (node (ref "U3") (pin "3") (pinfunction "VOUT_3") (pintype "passive"))
      (node (ref "停车触发接口") (pin "2") (pinfunction "2_2") (pintype "passive"))
      (node (ref "无线串口模块") (pin "7") (pinfunction "7_7") (pintype "passive"))
      (node (ref "有去") (pin "1") (pinfunction "1_1") (pintype "passive"))
      (node (ref "有来") (pin "1") (pinfunction "1_1") (pintype "passive"))
      (node (ref "编码器1") (pin "5") (pinfunction "5_5") (pintype "passive"))
      (node (ref "编码器2") (pin "5") (pinfunction "5_5") (pintype "passive"))
    )
    (net (code "82") (name "VCCBAT") (class "Default")
      (node (ref "C3") (pin "2") (pinfunction "2_2") (pintype "passive"))
      (node (ref "C4") (pin "1") (pinfunction "1_1") (pintype "passive"))
      (node (ref "C5") (pin "1") (pinfunction "1_1") (pintype "passive"))
      (node (ref "D2") (pin "A") (pinfunction "A_A") (pintype "passive"))
      (node (ref "DCOUT1") (pin "1") (pinfunction "1_1") (pintype "passive"))
      (node (ref "Q1") (pin "1") (pinfunction "D_1") (pintype "passive"))
      (node (ref "R10") (pin "2") (pinfunction "2_2") (pintype "passive"))
      (node (ref "R8") (pin "1") (pinfunction "1_1") (pintype "passive"))
      (node (ref "U1") (pin "7") (pinfunction "VIN_7") (pintype "passive"))
      (node (ref "U1") (pin "8") (pinfunction "VIN_8") (pintype "passive"))
    )
    (net (code "83") (name "VCCSteer") (class "Default")
      (node (ref "C7") (pin "1") (pinfunction "1_1") (pintype "passive"))
      (node (ref "C8") (pin "2") (pinfunction "2_2") (pintype "passive"))
      (node (ref "L1") (pin "1") (pinfunction "1_1") (pintype "passive"))
      (node (ref "R13") (pin "1") (pinfunction "1_1") (pintype "passive"))
      (node (ref "R7") (pin "1") (pinfunction "1_1") (pintype "passive"))
      (node (ref "Steer") (pin "2") (pinfunction "2_2") (pintype "passive"))
    )
    (net (code "84") (name "unconnected-(CCD1-Pad3)") (class "Default")
      (node (ref "CCD1") (pin "3") (pinfunction "3_3") (pintype "passive+no_connect"))
    )
    (net (code "85") (name "unconnected-(CCD2-Pad3)") (class "Default")
      (node (ref "CCD2") (pin "3") (pinfunction "3_3") (pintype "passive+no_connect"))
    )
    (net (code "86") (name "unconnected-(H1-Pad11)") (class "Default")
      (node (ref "H1") (pin "11") (pinfunction "11_11") (pintype "passive"))
    )
    (net (code "87") (name "unconnected-(H2-Pad11)") (class "Default")
      (node (ref "H2") (pin "11") (pinfunction "11_11") (pintype "passive"))
    )
    (net (code "88") (name "unconnected-(H3-Pad11)") (class "Default")
      (node (ref "H3") (pin "11") (pinfunction "11_11") (pintype "passive"))
    )
    (net (code "89") (name "unconnected-(H4-Pad11)") (class "Default")
      (node (ref "H4") (pin "11") (pinfunction "11_11") (pintype "passive"))
    )
    (net (code "90") (name "unconnected-(MPU-CS-Pad6)") (class "Default")
      (node (ref "MPU") (pin "6") (pinfunction "CS_6") (pintype "passive+no_connect"))
    )
    (net (code "91") (name "unconnected-(MPU-FSY-Pad8)") (class "Default")
      (node (ref "MPU") (pin "8") (pinfunction "FSY_8") (pintype "passive+no_connect"))
    )
    (net (code "92") (name "unconnected-(MPU-INT-Pad7)") (class "Default")
      (node (ref "MPU") (pin "7") (pinfunction "INT_7") (pintype "passive+no_connect"))
    )
    (net (code "93") (name "unconnected-(MPU-SA0-Pad5)") (class "Default")
      (node (ref "MPU") (pin "5") (pinfunction "SA0_5") (pintype "passive+no_connect"))
    )
    (net (code "94") (name "unconnected-(R3-TOP-Pad1)") (class "Default")
      (node (ref "R3") (pin "1") (pinfunction "TOP_1") (pintype "passive"))
    )
    (net (code "95") (name "unconnected-(U2-2.4-Pad46)") (class "Default")
      (node (ref "U2") (pin "46") (pinfunction "2.4_46") (pintype "passive"))
    )
    (net (code "96") (name "unconnected-(U2-4.4-Pad13)") (class "Default")
      (node (ref "U2") (pin "13") (pinfunction "4.4_13") (pintype "passive"))
    )
    (net (code "97") (name "unconnected-(U2-4.5-Pad64)") (class "Default")
      (node (ref "U2") (pin "64") (pinfunction "4.5_64") (pintype "passive"))
    )
    (net (code "98") (name "unconnected-(U2-4.7-Pad20)") (class "Default")
      (node (ref "U2") (pin "20") (pinfunction "4.7_20") (pintype "passive"))
    )
    (net (code "99") (name "unconnected-(U2-5.2-Pad4)") (class "Default")
      (node (ref "U2") (pin "4") (pinfunction "5.2_4") (pintype "passive"))
    )
    (net (code "100") (name "unconnected-(U2-6.1-Pad9)") (class "Default")
      (node (ref "U2") (pin "9") (pinfunction "6.1_9") (pintype "passive"))
    )
    (net (code "101") (name "unconnected-(U2-6.3-Pad11)") (class "Default")
      (node (ref "U2") (pin "11") (pinfunction "6.3_11") (pintype "passive"))
    )
    (net (code "102") (name "unconnected-(U2-6.5-Pad21)") (class "Default")
      (node (ref "U2") (pin "21") (pinfunction "6.5_21") (pintype "passive"))
    )
    (net (code "103") (name "unconnected-(U2-6.7-Pad23)") (class "Default")
      (node (ref "U2") (pin "23") (pinfunction "6.7_23") (pintype "passive"))
    )
    (net (code "104") (name "unconnected-(U2-7.1-Pad38)") (class "Default")
      (node (ref "U2") (pin "38") (pinfunction "7.1_38") (pintype "passive"))
    )
    (net (code "105") (name "unconnected-(U2-7.2-Pad37)") (class "Default")
      (node (ref "U2") (pin "37") (pinfunction "7.2_37") (pintype "passive"))
    )
    (net (code "106") (name "unconnected-(U2-7.3-Pad40)") (class "Default")
      (node (ref "U2") (pin "40") (pinfunction "7.3_40") (pintype "passive"))
    )
    (net (code "107") (name "unconnected-(U2-UCAP-Pad8)") (class "Default")
      (node (ref "U2") (pin "8") (pinfunction "UCAP_8") (pintype "passive"))
    )
    (net (code "108") (name "unconnected-(无线串口模块-Pad2)") (class "Default")
      (node (ref "无线串口模块") (pin "2") (pinfunction "2_2") (pintype "passive+no_connect"))
    )
    (net (code "109") (name "unconnected-(无线串口模块-Pad8)") (class "Default")
      (node (ref "无线串口模块") (pin "8") (pinfunction "8_8") (pintype "passive+no_connect"))
    )
    (net (code "110") (name "unconnected-(有去-Pad4)") (class "Default")
      (node (ref "有去") (pin "4") (pinfunction "4_4") (pintype "passive+no_connect"))
    )
    (net (code "111") (name "unconnected-(编码器1-Pad1)") (class "Default")
      (node (ref "编码器1") (pin "1") (pinfunction "1_1") (pintype "passive+no_connect"))
    )
    (net (code "112") (name "unconnected-(编码器1-Pad2)") (class "Default")
      (node (ref "编码器1") (pin "2") (pinfunction "2_2") (pintype "passive+no_connect"))
    )
    (net (code "113") (name "unconnected-(编码器2-Pad1)") (class "Default")
      (node (ref "编码器2") (pin "1") (pinfunction "1_1") (pintype "passive+no_connect"))
    )
    (net (code "114") (name "unconnected-(编码器2-Pad2)") (class "Default")
      (node (ref "编码器2") (pin "2") (pinfunction "2_2") (pintype "passive+no_connect"))
    )
  )
)
